# d100_zm1000_rev_b.net
KiCad netlist of a schematic drawn in EAGLE
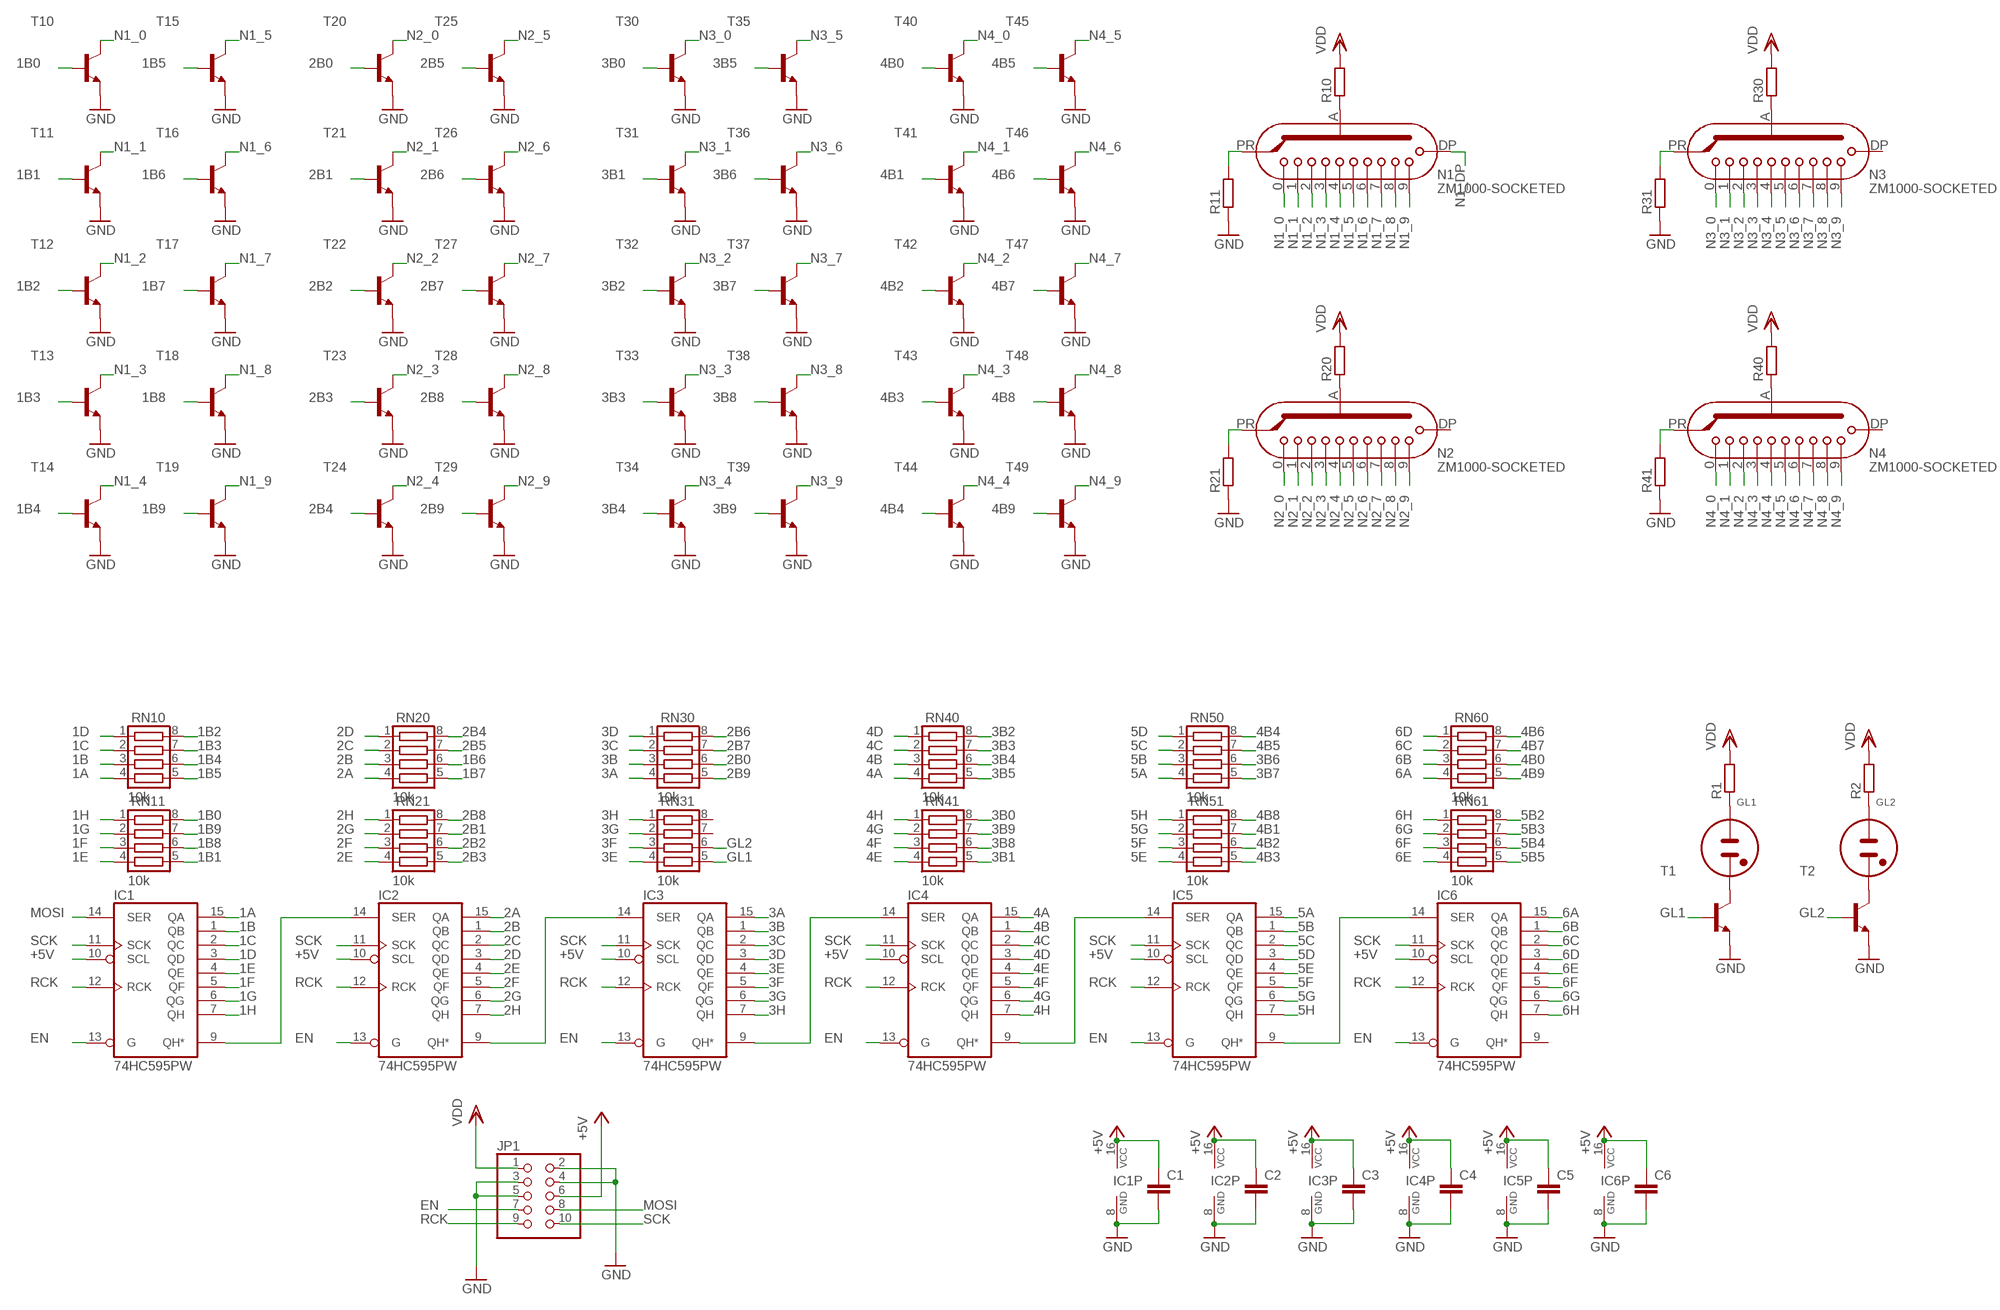
[diagram p0: schematic, sheet 1]

(export (version "E")
  (design (tool "Eeschema 10.0.6"))
  (components
    (comp (ref "C1")
      (value "C-EUC0603")
      (footprint "eagle-import:C0603")
      (libsource (lib "eagle-import") (part "C-EUC0603"))
    )
    (comp (ref "C2")
      (value "C-EUC0603")
      (footprint "eagle-import:C0603")
      (libsource (lib "eagle-import") (part "C-EUC0603"))
    )
    (comp (ref "C3")
      (value "C-EUC0603")
      (footprint "eagle-import:C0603")
      (libsource (lib "eagle-import") (part "C-EUC0603"))
    )
    (comp (ref "C4")
      (value "C-EUC0603")
      (footprint "eagle-import:C0603")
      (libsource (lib "eagle-import") (part "C-EUC0603"))
    )
    (comp (ref "C5")
      (value "C-EUC0603")
      (footprint "eagle-import:C0603")
      (libsource (lib "eagle-import") (part "C-EUC0603"))
    )
    (comp (ref "C6")
      (value "C-EUC0603")
      (footprint "eagle-import:C0603")
      (libsource (lib "eagle-import") (part "C-EUC0603"))
    )
    (comp (ref "GL1")
      (value "NE2-NEON-BULB-DRILL")
      (footprint "eagle-import:NE2-NEON-BULB-DRILL")
      (libsource (lib "eagle-import") (part "NE2-NEON-BULB-DRILL"))
    )
    (comp (ref "GL2")
      (value "NE2-NEON-BULB-DRILL")
      (footprint "eagle-import:NE2-NEON-BULB-DRILL")
      (libsource (lib "eagle-import") (part "NE2-NEON-BULB-DRILL"))
    )
    (comp (ref "IC1")
      (value "74HC595PW")
      (footprint "eagle-import:TSSOP16")
      (libsource (lib "eagle-import") (part "74595PWHC"))
    )
    (comp (ref "IC2")
      (value "74HC595PW")
      (footprint "eagle-import:TSSOP16")
      (libsource (lib "eagle-import") (part "74595PWHC"))
    )
    (comp (ref "IC3")
      (value "74HC595PW")
      (footprint "eagle-import:TSSOP16")
      (libsource (lib "eagle-import") (part "74595PWHC"))
    )
    (comp (ref "IC4")
      (value "74HC595PW")
      (footprint "eagle-import:TSSOP16")
      (libsource (lib "eagle-import") (part "74595PWHC"))
    )
    (comp (ref "IC5")
      (value "74HC595PW")
      (footprint "eagle-import:TSSOP16")
      (libsource (lib "eagle-import") (part "74595PWHC"))
    )
    (comp (ref "IC6")
      (value "74HC595PW")
      (footprint "eagle-import:TSSOP16")
      (libsource (lib "eagle-import") (part "74595PWHC"))
    )
    (comp (ref "JP1")
      (value "PINHD-2X5_2.54-SMD")
      (footprint "eagle-import:2X05SMD")
      (libsource (lib "eagle-import") (part "PINHD-2X5_2.54-SMD"))
    )
    (comp (ref "N1")
      (value "ZM1000-SOCKETED")
      (footprint "eagle-import:ZM1000-SOCKETED")
      (libsource (lib "eagle-import") (part "ZM1000-SOCKETED"))
    )
    (comp (ref "N2")
      (value "ZM1000-SOCKETED")
      (footprint "eagle-import:ZM1000-SOCKETED")
      (libsource (lib "eagle-import") (part "ZM1000-SOCKETED"))
    )
    (comp (ref "N3")
      (value "ZM1000-SOCKETED")
      (footprint "eagle-import:ZM1000-SOCKETED")
      (libsource (lib "eagle-import") (part "ZM1000-SOCKETED"))
    )
    (comp (ref "N4")
      (value "ZM1000-SOCKETED")
      (footprint "eagle-import:ZM1000-SOCKETED")
      (libsource (lib "eagle-import") (part "ZM1000-SOCKETED"))
    )
    (comp (ref "R1")
      (value "R-EU_R0603")
      (footprint "eagle-import:R0603")
      (libsource (lib "eagle-import") (part "R-EU_R0603"))
    )
    (comp (ref "R2")
      (value "R-EU_R0603")
      (footprint "eagle-import:R0603")
      (libsource (lib "eagle-import") (part "R-EU_R0603"))
    )
    (comp (ref "R10")
      (value "R-EU_R0603")
      (footprint "eagle-import:R0603")
      (libsource (lib "eagle-import") (part "R-EU_R0603"))
    )
    (comp (ref "R11")
      (value "R-EU_R0603")
      (footprint "eagle-import:R0603")
      (libsource (lib "eagle-import") (part "R-EU_R0603"))
    )
    (comp (ref "R20")
      (value "R-EU_R0603")
      (footprint "eagle-import:R0603")
      (libsource (lib "eagle-import") (part "R-EU_R0603"))
    )
    (comp (ref "R21")
      (value "R-EU_R0603")
      (footprint "eagle-import:R0603")
      (libsource (lib "eagle-import") (part "R-EU_R0603"))
    )
    (comp (ref "R30")
      (value "R-EU_R0603")
      (footprint "eagle-import:R0603")
      (libsource (lib "eagle-import") (part "R-EU_R0603"))
    )
    (comp (ref "R31")
      (value "R-EU_R0603")
      (footprint "eagle-import:R0603")
      (libsource (lib "eagle-import") (part "R-EU_R0603"))
    )
    (comp (ref "R40")
      (value "R-EU_R0603")
      (footprint "eagle-import:R0603")
      (libsource (lib "eagle-import") (part "R-EU_R0603"))
    )
    (comp (ref "R41")
      (value "R-EU_R0603")
      (footprint "eagle-import:R0603")
      (libsource (lib "eagle-import") (part "R-EU_R0603"))
    )
    (comp (ref "RN10")
      (value "10k")
      (footprint "eagle-import:CTS742C083")
      (fields (field (name "OC_FARNELL") "unknown") (field (name "OC_NEWARK") "unknown"))
      (libsource (lib "eagle-import") (part "CTS742C083"))
    )
    (comp (ref "RN11")
      (value "10k")
      (footprint "eagle-import:CTS742C083")
      (fields (field (name "OC_FARNELL") "unknown") (field (name "OC_NEWARK") "unknown"))
      (libsource (lib "eagle-import") (part "CTS742C083"))
    )
    (comp (ref "RN20")
      (value "10k")
      (footprint "eagle-import:CTS742C083")
      (fields (field (name "OC_FARNELL") "unknown") (field (name "OC_NEWARK") "unknown"))
      (libsource (lib "eagle-import") (part "CTS742C083"))
    )
    (comp (ref "RN21")
      (value "10k")
      (footprint "eagle-import:CTS742C083")
      (fields (field (name "OC_FARNELL") "unknown") (field (name "OC_NEWARK") "unknown"))
      (libsource (lib "eagle-import") (part "CTS742C083"))
    )
    (comp (ref "RN30")
      (value "10k")
      (footprint "eagle-import:CTS742C083")
      (fields (field (name "OC_FARNELL") "unknown") (field (name "OC_NEWARK") "unknown"))
      (libsource (lib "eagle-import") (part "CTS742C083"))
    )
    (comp (ref "RN31")
      (value "10k")
      (footprint "eagle-import:CTS742C083")
      (fields (field (name "OC_FARNELL") "unknown") (field (name "OC_NEWARK") "unknown"))
      (libsource (lib "eagle-import") (part "CTS742C083"))
    )
    (comp (ref "RN40")
      (value "10k")
      (footprint "eagle-import:CTS742C083")
      (fields (field (name "OC_FARNELL") "unknown") (field (name "OC_NEWARK") "unknown"))
      (libsource (lib "eagle-import") (part "CTS742C083"))
    )
    (comp (ref "RN41")
      (value "10k")
      (footprint "eagle-import:CTS742C083")
      (fields (field (name "OC_FARNELL") "unknown") (field (name "OC_NEWARK") "unknown"))
      (libsource (lib "eagle-import") (part "CTS742C083"))
    )
    (comp (ref "RN50")
      (value "10k")
      (footprint "eagle-import:CTS742C083")
      (fields (field (name "OC_FARNELL") "unknown") (field (name "OC_NEWARK") "unknown"))
      (libsource (lib "eagle-import") (part "CTS742C083"))
    )
    (comp (ref "RN51")
      (value "10k")
      (footprint "eagle-import:CTS742C083")
      (fields (field (name "OC_FARNELL") "unknown") (field (name "OC_NEWARK") "unknown"))
      (libsource (lib "eagle-import") (part "CTS742C083"))
    )
    (comp (ref "RN60")
      (value "10k")
      (footprint "eagle-import:CTS742C083")
      (fields (field (name "OC_FARNELL") "unknown") (field (name "OC_NEWARK") "unknown"))
      (libsource (lib "eagle-import") (part "CTS742C083"))
    )
    (comp (ref "RN61")
      (value "10k")
      (footprint "eagle-import:CTS742C083")
      (fields (field (name "OC_FARNELL") "unknown") (field (name "OC_NEWARK") "unknown"))
      (libsource (lib "eagle-import") (part "CTS742C083"))
    )
    (comp (ref "T1")
      (value "SMBTA42")
      (footprint "eagle-import:SOT23")
      (libsource (lib "eagle-import") (part "SMBTA42"))
    )
    (comp (ref "T2")
      (value "SMBTA42")
      (footprint "eagle-import:SOT23")
      (libsource (lib "eagle-import") (part "SMBTA42"))
    )
    (comp (ref "T10")
      (value "SMBTA42")
      (footprint "eagle-import:SOT23")
      (libsource (lib "eagle-import") (part "SMBTA42"))
    )
    (comp (ref "T11")
      (value "SMBTA42")
      (footprint "eagle-import:SOT23")
      (libsource (lib "eagle-import") (part "SMBTA42"))
    )
    (comp (ref "T12")
      (value "SMBTA42")
      (footprint "eagle-import:SOT23")
      (libsource (lib "eagle-import") (part "SMBTA42"))
    )
    (comp (ref "T13")
      (value "SMBTA42")
      (footprint "eagle-import:SOT23")
      (libsource (lib "eagle-import") (part "SMBTA42"))
    )
    (comp (ref "T14")
      (value "SMBTA42")
      (footprint "eagle-import:SOT23")
      (libsource (lib "eagle-import") (part "SMBTA42"))
    )
    (comp (ref "T15")
      (value "SMBTA42")
      (footprint "eagle-import:SOT23")
      (libsource (lib "eagle-import") (part "SMBTA42"))
    )
    (comp (ref "T16")
      (value "SMBTA42")
      (footprint "eagle-import:SOT23")
      (libsource (lib "eagle-import") (part "SMBTA42"))
    )
    (comp (ref "T17")
      (value "SMBTA42")
      (footprint "eagle-import:SOT23")
      (libsource (lib "eagle-import") (part "SMBTA42"))
    )
    (comp (ref "T18")
      (value "SMBTA42")
      (footprint "eagle-import:SOT23")
      (libsource (lib "eagle-import") (part "SMBTA42"))
    )
    (comp (ref "T19")
      (value "SMBTA42")
      (footprint "eagle-import:SOT23")
      (libsource (lib "eagle-import") (part "SMBTA42"))
    )
    (comp (ref "T20")
      (value "SMBTA42")
      (footprint "eagle-import:SOT23")
      (libsource (lib "eagle-import") (part "SMBTA42"))
    )
    (comp (ref "T21")
      (value "SMBTA42")
      (footprint "eagle-import:SOT23")
      (libsource (lib "eagle-import") (part "SMBTA42"))
    )
    (comp (ref "T22")
      (value "SMBTA42")
      (footprint "eagle-import:SOT23")
      (libsource (lib "eagle-import") (part "SMBTA42"))
    )
    (comp (ref "T23")
      (value "SMBTA42")
      (footprint "eagle-import:SOT23")
      (libsource (lib "eagle-import") (part "SMBTA42"))
    )
    (comp (ref "T24")
      (value "SMBTA42")
      (footprint "eagle-import:SOT23")
      (libsource (lib "eagle-import") (part "SMBTA42"))
    )
    (comp (ref "T25")
      (value "SMBTA42")
      (footprint "eagle-import:SOT23")
      (libsource (lib "eagle-import") (part "SMBTA42"))
    )
    (comp (ref "T26")
      (value "SMBTA42")
      (footprint "eagle-import:SOT23")
      (libsource (lib "eagle-import") (part "SMBTA42"))
    )
    (comp (ref "T27")
      (value "SMBTA42")
      (footprint "eagle-import:SOT23")
      (libsource (lib "eagle-import") (part "SMBTA42"))
    )
    (comp (ref "T28")
      (value "SMBTA42")
      (footprint "eagle-import:SOT23")
      (libsource (lib "eagle-import") (part "SMBTA42"))
    )
    (comp (ref "T29")
      (value "SMBTA42")
      (footprint "eagle-import:SOT23")
      (libsource (lib "eagle-import") (part "SMBTA42"))
    )
    (comp (ref "T30")
      (value "SMBTA42")
      (footprint "eagle-import:SOT23")
      (libsource (lib "eagle-import") (part "SMBTA42"))
    )
    (comp (ref "T31")
      (value "SMBTA42")
      (footprint "eagle-import:SOT23")
      (libsource (lib "eagle-import") (part "SMBTA42"))
    )
    (comp (ref "T32")
      (value "SMBTA42")
      (footprint "eagle-import:SOT23")
      (libsource (lib "eagle-import") (part "SMBTA42"))
    )
    (comp (ref "T33")
      (value "SMBTA42")
      (footprint "eagle-import:SOT23")
      (libsource (lib "eagle-import") (part "SMBTA42"))
    )
    (comp (ref "T34")
      (value "SMBTA42")
      (footprint "eagle-import:SOT23")
      (libsource (lib "eagle-import") (part "SMBTA42"))
    )
    (comp (ref "T35")
      (value "SMBTA42")
      (footprint "eagle-import:SOT23")
      (libsource (lib "eagle-import") (part "SMBTA42"))
    )
    (comp (ref "T36")
      (value "SMBTA42")
      (footprint "eagle-import:SOT23")
      (libsource (lib "eagle-import") (part "SMBTA42"))
    )
    (comp (ref "T37")
      (value "SMBTA42")
      (footprint "eagle-import:SOT23")
      (libsource (lib "eagle-import") (part "SMBTA42"))
    )
    (comp (ref "T38")
      (value "SMBTA42")
      (footprint "eagle-import:SOT23")
      (libsource (lib "eagle-import") (part "SMBTA42"))
    )
    (comp (ref "T39")
      (value "SMBTA42")
      (footprint "eagle-import:SOT23")
      (libsource (lib "eagle-import") (part "SMBTA42"))
    )
    (comp (ref "T40")
      (value "SMBTA42")
      (footprint "eagle-import:SOT23")
      (libsource (lib "eagle-import") (part "SMBTA42"))
    )
    (comp (ref "T41")
      (value "SMBTA42")
      (footprint "eagle-import:SOT23")
      (libsource (lib "eagle-import") (part "SMBTA42"))
    )
    (comp (ref "T42")
      (value "SMBTA42")
      (footprint "eagle-import:SOT23")
      (libsource (lib "eagle-import") (part "SMBTA42"))
    )
    (comp (ref "T43")
      (value "SMBTA42")
      (footprint "eagle-import:SOT23")
      (libsource (lib "eagle-import") (part "SMBTA42"))
    )
    (comp (ref "T44")
      (value "SMBTA42")
      (footprint "eagle-import:SOT23")
      (libsource (lib "eagle-import") (part "SMBTA42"))
    )
    (comp (ref "T45")
      (value "SMBTA42")
      (footprint "eagle-import:SOT23")
      (libsource (lib "eagle-import") (part "SMBTA42"))
    )
    (comp (ref "T46")
      (value "SMBTA42")
      (footprint "eagle-import:SOT23")
      (libsource (lib "eagle-import") (part "SMBTA42"))
    )
    (comp (ref "T47")
      (value "SMBTA42")
      (footprint "eagle-import:SOT23")
      (libsource (lib "eagle-import") (part "SMBTA42"))
    )
    (comp (ref "T48")
      (value "SMBTA42")
      (footprint "eagle-import:SOT23")
      (libsource (lib "eagle-import") (part "SMBTA42"))
    )
    (comp (ref "T49")
      (value "SMBTA42")
      (footprint "eagle-import:SOT23")
      (libsource (lib "eagle-import") (part "SMBTA42"))
    )
  )
  (nets
    (net (code "1") (name "+5V") (class "Default")
      (node (ref "C1") (pin "1") (pinfunction "1_1") (pintype "passive"))
      (node (ref "C2") (pin "1") (pinfunction "1_1") (pintype "passive"))
      (node (ref "C3") (pin "1") (pinfunction "1_1") (pintype "passive"))
      (node (ref "C4") (pin "1") (pinfunction "1_1") (pintype "passive"))
      (node (ref "C5") (pin "1") (pinfunction "1_1") (pintype "passive"))
      (node (ref "C6") (pin "1") (pinfunction "1_1") (pintype "passive"))
      (node (ref "IC1") (pin "10") (pinfunction "SCL_10") (pintype "input"))
      (node (ref "IC1") (pin "16") (pinfunction "VCC_16") (pintype "power_in"))
      (node (ref "IC2") (pin "10") (pinfunction "SCL_10") (pintype "input"))
      (node (ref "IC2") (pin "16") (pinfunction "VCC_16") (pintype "power_in"))
      (node (ref "IC3") (pin "10") (pinfunction "SCL_10") (pintype "input"))
      (node (ref "IC3") (pin "16") (pinfunction "VCC_16") (pintype "power_in"))
      (node (ref "IC4") (pin "10") (pinfunction "SCL_10") (pintype "input"))
      (node (ref "IC4") (pin "16") (pinfunction "VCC_16") (pintype "power_in"))
      (node (ref "IC5") (pin "10") (pinfunction "SCL_10") (pintype "input"))
      (node (ref "IC5") (pin "16") (pinfunction "VCC_16") (pintype "power_in"))
      (node (ref "IC6") (pin "10") (pinfunction "SCL_10") (pintype "input"))
      (node (ref "IC6") (pin "16") (pinfunction "VCC_16") (pintype "power_in"))
      (node (ref "JP1") (pin "6") (pinfunction "6_6") (pintype "passive"))
    )
    (net (code "2") (name "/1A") (class "Default")
      (node (ref "IC1") (pin "15") (pinfunction "QA_15") (pintype "tri_state"))
      (node (ref "RN10") (pin "4") (pinfunction "4_4") (pintype "passive"))
    )
    (net (code "3") (name "/1B") (class "Default")
      (node (ref "IC1") (pin "1") (pinfunction "QB_1") (pintype "tri_state"))
      (node (ref "RN10") (pin "3") (pinfunction "3_3") (pintype "passive"))
    )
    (net (code "4") (name "/1B0") (class "Default")
      (node (ref "RN11") (pin "8") (pinfunction "8_8") (pintype "passive"))
      (node (ref "T10") (pin "1") (pinfunction "B_1") (pintype "passive"))
    )
    (net (code "5") (name "/1B1") (class "Default")
      (node (ref "RN11") (pin "5") (pinfunction "5_5") (pintype "passive"))
      (node (ref "T11") (pin "1") (pinfunction "B_1") (pintype "passive"))
    )
    (net (code "6") (name "/1B2") (class "Default")
      (node (ref "RN10") (pin "8") (pinfunction "8_8") (pintype "passive"))
      (node (ref "T12") (pin "1") (pinfunction "B_1") (pintype "passive"))
    )
    (net (code "7") (name "/1B3") (class "Default")
      (node (ref "RN10") (pin "7") (pinfunction "7_7") (pintype "passive"))
      (node (ref "T13") (pin "1") (pinfunction "B_1") (pintype "passive"))
    )
    (net (code "8") (name "/1B4") (class "Default")
      (node (ref "RN10") (pin "6") (pinfunction "6_6") (pintype "passive"))
      (node (ref "T14") (pin "1") (pinfunction "B_1") (pintype "passive"))
    )
    (net (code "9") (name "/1B5") (class "Default")
      (node (ref "RN10") (pin "5") (pinfunction "5_5") (pintype "passive"))
      (node (ref "T15") (pin "1") (pinfunction "B_1") (pintype "passive"))
    )
    (net (code "10") (name "/1B6") (class "Default")
      (node (ref "RN20") (pin "6") (pinfunction "6_6") (pintype "passive"))
      (node (ref "T16") (pin "1") (pinfunction "B_1") (pintype "passive"))
    )
    (net (code "11") (name "/1B7") (class "Default")
      (node (ref "RN20") (pin "5") (pinfunction "5_5") (pintype "passive"))
      (node (ref "T17") (pin "1") (pinfunction "B_1") (pintype "passive"))
    )
    (net (code "12") (name "/1B8") (class "Default")
      (node (ref "RN11") (pin "6") (pinfunction "6_6") (pintype "passive"))
      (node (ref "T18") (pin "1") (pinfunction "B_1") (pintype "passive"))
    )
    (net (code "13") (name "/1B9") (class "Default")
      (node (ref "RN11") (pin "7") (pinfunction "7_7") (pintype "passive"))
      (node (ref "T19") (pin "1") (pinfunction "B_1") (pintype "passive"))
    )
    (net (code "14") (name "/1C") (class "Default")
      (node (ref "IC1") (pin "2") (pinfunction "QC_2") (pintype "tri_state"))
      (node (ref "RN10") (pin "2") (pinfunction "2_2") (pintype "passive"))
    )
    (net (code "15") (name "/1D") (class "Default")
      (node (ref "IC1") (pin "3") (pinfunction "QD_3") (pintype "tri_state"))
      (node (ref "RN10") (pin "1") (pinfunction "1_1") (pintype "passive"))
    )
    (net (code "16") (name "/1E") (class "Default")
      (node (ref "IC1") (pin "4") (pinfunction "QE_4") (pintype "tri_state"))
      (node (ref "RN11") (pin "4") (pinfunction "4_4") (pintype "passive"))
    )
    (net (code "17") (name "/1F") (class "Default")
      (node (ref "IC1") (pin "5") (pinfunction "QF_5") (pintype "tri_state"))
      (node (ref "RN11") (pin "3") (pinfunction "3_3") (pintype "passive"))
    )
    (net (code "18") (name "/1G") (class "Default")
      (node (ref "IC1") (pin "6") (pinfunction "QG_6") (pintype "tri_state"))
      (node (ref "RN11") (pin "2") (pinfunction "2_2") (pintype "passive"))
    )
    (net (code "19") (name "/1H") (class "Default")
      (node (ref "IC1") (pin "7") (pinfunction "QH_7") (pintype "tri_state"))
      (node (ref "RN11") (pin "1") (pinfunction "1_1") (pintype "passive"))
    )
    (net (code "20") (name "/2A") (class "Default")
      (node (ref "IC2") (pin "15") (pinfunction "QA_15") (pintype "tri_state"))
      (node (ref "RN20") (pin "4") (pinfunction "4_4") (pintype "passive"))
    )
    (net (code "21") (name "/2B") (class "Default")
      (node (ref "IC2") (pin "1") (pinfunction "QB_1") (pintype "tri_state"))
      (node (ref "RN20") (pin "3") (pinfunction "3_3") (pintype "passive"))
    )
    (net (code "22") (name "/2B0") (class "Default")
      (node (ref "RN30") (pin "6") (pinfunction "6_6") (pintype "passive"))
      (node (ref "T20") (pin "1") (pinfunction "B_1") (pintype "passive"))
    )
    (net (code "23") (name "/2B1") (class "Default")
      (node (ref "RN21") (pin "7") (pinfunction "7_7") (pintype "passive"))
      (node (ref "T21") (pin "1") (pinfunction "B_1") (pintype "passive"))
    )
    (net (code "24") (name "/2B2") (class "Default")
      (node (ref "RN21") (pin "6") (pinfunction "6_6") (pintype "passive"))
      (node (ref "T22") (pin "1") (pinfunction "B_1") (pintype "passive"))
    )
    (net (code "25") (name "/2B3") (class "Default")
      (node (ref "RN21") (pin "5") (pinfunction "5_5") (pintype "passive"))
      (node (ref "T23") (pin "1") (pinfunction "B_1") (pintype "passive"))
    )
    (net (code "26") (name "/2B4") (class "Default")
      (node (ref "RN20") (pin "8") (pinfunction "8_8") (pintype "passive"))
      (node (ref "T24") (pin "1") (pinfunction "B_1") (pintype "passive"))
    )
    (net (code "27") (name "/2B5") (class "Default")
      (node (ref "RN20") (pin "7") (pinfunction "7_7") (pintype "passive"))
      (node (ref "T25") (pin "1") (pinfunction "B_1") (pintype "passive"))
    )
    (net (code "28") (name "/2B6") (class "Default")
      (node (ref "RN30") (pin "8") (pinfunction "8_8") (pintype "passive"))
      (node (ref "T26") (pin "1") (pinfunction "B_1") (pintype "passive"))
    )
    (net (code "29") (name "/2B7") (class "Default")
      (node (ref "RN30") (pin "7") (pinfunction "7_7") (pintype "passive"))
      (node (ref "T27") (pin "1") (pinfunction "B_1") (pintype "passive"))
    )
    (net (code "30") (name "/2B8") (class "Default")
      (node (ref "RN21") (pin "8") (pinfunction "8_8") (pintype "passive"))
      (node (ref "T28") (pin "1") (pinfunction "B_1") (pintype "passive"))
    )
    (net (code "31") (name "/2B9") (class "Default")
      (node (ref "RN30") (pin "5") (pinfunction "5_5") (pintype "passive"))
      (node (ref "T29") (pin "1") (pinfunction "B_1") (pintype "passive"))
    )
    (net (code "32") (name "/2C") (class "Default")
      (node (ref "IC2") (pin "2") (pinfunction "QC_2") (pintype "tri_state"))
      (node (ref "RN20") (pin "2") (pinfunction "2_2") (pintype "passive"))
    )
    (net (code "33") (name "/2D") (class "Default")
      (node (ref "IC2") (pin "3") (pinfunction "QD_3") (pintype "tri_state"))
      (node (ref "RN20") (pin "1") (pinfunction "1_1") (pintype "passive"))
    )
    (net (code "34") (name "/2E") (class "Default")
      (node (ref "IC2") (pin "4") (pinfunction "QE_4") (pintype "tri_state"))
      (node (ref "RN21") (pin "4") (pinfunction "4_4") (pintype "passive"))
    )
    (net (code "35") (name "/2F") (class "Default")
      (node (ref "IC2") (pin "5") (pinfunction "QF_5") (pintype "tri_state"))
      (node (ref "RN21") (pin "3") (pinfunction "3_3") (pintype "passive"))
    )
    (net (code "36") (name "/2G") (class "Default")
      (node (ref "IC2") (pin "6") (pinfunction "QG_6") (pintype "tri_state"))
      (node (ref "RN21") (pin "2") (pinfunction "2_2") (pintype "passive"))
    )
    (net (code "37") (name "/2H") (class "Default")
      (node (ref "IC2") (pin "7") (pinfunction "QH_7") (pintype "tri_state"))
      (node (ref "RN21") (pin "1") (pinfunction "1_1") (pintype "passive"))
    )
    (net (code "38") (name "/3A") (class "Default")
      (node (ref "IC3") (pin "15") (pinfunction "QA_15") (pintype "tri_state"))
      (node (ref "RN30") (pin "4") (pinfunction "4_4") (pintype "passive"))
    )
    (net (code "39") (name "/3B") (class "Default")
      (node (ref "IC3") (pin "1") (pinfunction "QB_1") (pintype "tri_state"))
      (node (ref "RN30") (pin "3") (pinfunction "3_3") (pintype "passive"))
    )
    (net (code "40") (name "/3B0") (class "Default")
      (node (ref "RN41") (pin "8") (pinfunction "8_8") (pintype "passive"))
      (node (ref "T30") (pin "1") (pinfunction "B_1") (pintype "passive"))
    )
    (net (code "41") (name "/3B1") (class "Default")
      (node (ref "RN41") (pin "5") (pinfunction "5_5") (pintype "passive"))
      (node (ref "T31") (pin "1") (pinfunction "B_1") (pintype "passive"))
    )
    (net (code "42") (name "/3B2") (class "Default")
      (node (ref "RN40") (pin "8") (pinfunction "8_8") (pintype "passive"))
      (node (ref "T32") (pin "1") (pinfunction "B_1") (pintype "passive"))
    )
    (net (code "43") (name "/3B3") (class "Default")
      (node (ref "RN40") (pin "7") (pinfunction "7_7") (pintype "passive"))
      (node (ref "T33") (pin "1") (pinfunction "B_1") (pintype "passive"))
    )
    (net (code "44") (name "/3B4") (class "Default")
      (node (ref "RN40") (pin "6") (pinfunction "6_6") (pintype "passive"))
      (node (ref "T34") (pin "1") (pinfunction "B_1") (pintype "passive"))
    )
    (net (code "45") (name "/3B5") (class "Default")
      (node (ref "RN40") (pin "5") (pinfunction "5_5") (pintype "passive"))
      (node (ref "T35") (pin "1") (pinfunction "B_1") (pintype "passive"))
    )
    (net (code "46") (name "/3B6") (class "Default")
      (node (ref "RN50") (pin "6") (pinfunction "6_6") (pintype "passive"))
      (node (ref "T36") (pin "1") (pinfunction "B_1") (pintype "passive"))
    )
    (net (code "47") (name "/3B7") (class "Default")
      (node (ref "RN50") (pin "5") (pinfunction "5_5") (pintype "passive"))
      (node (ref "T37") (pin "1") (pinfunction "B_1") (pintype "passive"))
    )
    (net (code "48") (name "/3B8") (class "Default")
      (node (ref "RN41") (pin "6") (pinfunction "6_6") (pintype "passive"))
      (node (ref "T38") (pin "1") (pinfunction "B_1") (pintype "passive"))
    )
    (net (code "49") (name "/3B9") (class "Default")
      (node (ref "RN41") (pin "7") (pinfunction "7_7") (pintype "passive"))
      (node (ref "T39") (pin "1") (pinfunction "B_1") (pintype "passive"))
    )
    (net (code "50") (name "/3C") (class "Default")
      (node (ref "IC3") (pin "2") (pinfunction "QC_2") (pintype "tri_state"))
      (node (ref "RN30") (pin "2") (pinfunction "2_2") (pintype "passive"))
    )
    (net (code "51") (name "/3D") (class "Default")
      (node (ref "IC3") (pin "3") (pinfunction "QD_3") (pintype "tri_state"))
      (node (ref "RN30") (pin "1") (pinfunction "1_1") (pintype "passive"))
    )
    (net (code "52") (name "/3E") (class "Default")
      (node (ref "IC3") (pin "4") (pinfunction "QE_4") (pintype "tri_state"))
      (node (ref "RN31") (pin "4") (pinfunction "4_4") (pintype "passive"))
    )
    (net (code "53") (name "/3F") (class "Default")
      (node (ref "IC3") (pin "5") (pinfunction "QF_5") (pintype "tri_state"))
      (node (ref "RN31") (pin "3") (pinfunction "3_3") (pintype "passive"))
    )
    (net (code "54") (name "/3G") (class "Default")
      (node (ref "IC3") (pin "6") (pinfunction "QG_6") (pintype "tri_state"))
      (node (ref "RN31") (pin "2") (pinfunction "2_2") (pintype "passive"))
    )
    (net (code "55") (name "/3H") (class "Default")
      (node (ref "IC3") (pin "7") (pinfunction "QH_7") (pintype "tri_state"))
      (node (ref "RN31") (pin "1") (pinfunction "1_1") (pintype "passive"))
    )
    (net (code "56") (name "/4A") (class "Default")
      (node (ref "IC4") (pin "15") (pinfunction "QA_15") (pintype "tri_state"))
      (node (ref "RN40") (pin "4") (pinfunction "4_4") (pintype "passive"))
    )
    (net (code "57") (name "/4B") (class "Default")
      (node (ref "IC4") (pin "1") (pinfunction "QB_1") (pintype "tri_state"))
      (node (ref "RN40") (pin "3") (pinfunction "3_3") (pintype "passive"))
    )
    (net (code "58") (name "/4B0") (class "Default")
      (node (ref "RN60") (pin "6") (pinfunction "6_6") (pintype "passive"))
      (node (ref "T40") (pin "1") (pinfunction "B_1") (pintype "passive"))
    )
    (net (code "59") (name "/4B1") (class "Default")
      (node (ref "RN51") (pin "7") (pinfunction "7_7") (pintype "passive"))
      (node (ref "T41") (pin "1") (pinfunction "B_1") (pintype "passive"))
    )
    (net (code "60") (name "/4B2") (class "Default")
      (node (ref "RN51") (pin "6") (pinfunction "6_6") (pintype "passive"))
      (node (ref "T42") (pin "1") (pinfunction "B_1") (pintype "passive"))
    )
    (net (code "61") (name "/4B3") (class "Default")
      (node (ref "RN51") (pin "5") (pinfunction "5_5") (pintype "passive"))
      (node (ref "T43") (pin "1") (pinfunction "B_1") (pintype "passive"))
    )
    (net (code "62") (name "/4B4") (class "Default")
      (node (ref "RN50") (pin "8") (pinfunction "8_8") (pintype "passive"))
      (node (ref "T44") (pin "1") (pinfunction "B_1") (pintype "passive"))
    )
    (net (code "63") (name "/4B5") (class "Default")
      (node (ref "RN50") (pin "7") (pinfunction "7_7") (pintype "passive"))
      (node (ref "T45") (pin "1") (pinfunction "B_1") (pintype "passive"))
    )
    (net (code "64") (name "/4B6") (class "Default")
      (node (ref "RN60") (pin "8") (pinfunction "8_8") (pintype "passive"))
      (node (ref "T46") (pin "1") (pinfunction "B_1") (pintype "passive"))
    )
    (net (code "65") (name "/4B7") (class "Default")
      (node (ref "RN60") (pin "7") (pinfunction "7_7") (pintype "passive"))
      (node (ref "T47") (pin "1") (pinfunction "B_1") (pintype "passive"))
    )
    (net (code "66") (name "/4B8") (class "Default")
      (node (ref "RN51") (pin "8") (pinfunction "8_8") (pintype "passive"))
      (node (ref "T48") (pin "1") (pinfunction "B_1") (pintype "passive"))
    )
    (net (code "67") (name "/4B9") (class "Default")
      (node (ref "RN60") (pin "5") (pinfunction "5_5") (pintype "passive"))
      (node (ref "T49") (pin "1") (pinfunction "B_1") (pintype "passive"))
    )
    (net (code "68") (name "/4C") (class "Default")
      (node (ref "IC4") (pin "2") (pinfunction "QC_2") (pintype "tri_state"))
      (node (ref "RN40") (pin "2") (pinfunction "2_2") (pintype "passive"))
    )
    (net (code "69") (name "/4D") (class "Default")
      (node (ref "IC4") (pin "3") (pinfunction "QD_3") (pintype "tri_state"))
      (node (ref "RN40") (pin "1") (pinfunction "1_1") (pintype "passive"))
    )
    (net (code "70") (name "/4E") (class "Default")
      (node (ref "IC4") (pin "4") (pinfunction "QE_4") (pintype "tri_state"))
      (node (ref "RN41") (pin "4") (pinfunction "4_4") (pintype "passive"))
    )
    (net (code "71") (name "/4F") (class "Default")
      (node (ref "IC4") (pin "5") (pinfunction "QF_5") (pintype "tri_state"))
      (node (ref "RN41") (pin "3") (pinfunction "3_3") (pintype "passive"))
    )
    (net (code "72") (name "/4G") (class "Default")
      (node (ref "IC4") (pin "6") (pinfunction "QG_6") (pintype "tri_state"))
      (node (ref "RN41") (pin "2") (pinfunction "2_2") (pintype "passive"))
    )
    (net (code "73") (name "/4H") (class "Default")
      (node (ref "IC4") (pin "7") (pinfunction "QH_7") (pintype "tri_state"))
      (node (ref "RN41") (pin "1") (pinfunction "1_1") (pintype "passive"))
    )
    (net (code "74") (name "/5A") (class "Default")
      (node (ref "IC5") (pin "15") (pinfunction "QA_15") (pintype "tri_state"))
      (node (ref "RN50") (pin "4") (pinfunction "4_4") (pintype "passive"))
    )
    (net (code "75") (name "/5B") (class "Default")
      (node (ref "IC5") (pin "1") (pinfunction "QB_1") (pintype "tri_state"))
      (node (ref "RN50") (pin "3") (pinfunction "3_3") (pintype "passive"))
    )
    (net (code "76") (name "/5B2") (class "Default")
      (node (ref "RN61") (pin "8") (pinfunction "8_8") (pintype "passive"))
    )
    (net (code "77") (name "/5B3") (class "Default")
      (node (ref "RN61") (pin "7") (pinfunction "7_7") (pintype "passive"))
    )
    (net (code "78") (name "/5B4") (class "Default")
      (node (ref "RN61") (pin "6") (pinfunction "6_6") (pintype "passive"))
    )
    (net (code "79") (name "/5B5") (class "Default")
      (node (ref "RN61") (pin "5") (pinfunction "5_5") (pintype "passive"))
    )
    (net (code "80") (name "/5C") (class "Default")
      (node (ref "IC5") (pin "2") (pinfunction "QC_2") (pintype "tri_state"))
      (node (ref "RN50") (pin "2") (pinfunction "2_2") (pintype "passive"))
    )
    (net (code "81") (name "/5D") (class "Default")
      (node (ref "IC5") (pin "3") (pinfunction "QD_3") (pintype "tri_state"))
      (node (ref "RN50") (pin "1") (pinfunction "1_1") (pintype "passive"))
    )
    (net (code "82") (name "/5E") (class "Default")
      (node (ref "IC5") (pin "4") (pinfunction "QE_4") (pintype "tri_state"))
      (node (ref "RN51") (pin "4") (pinfunction "4_4") (pintype "passive"))
    )
    (net (code "83") (name "/5F") (class "Default")
      (node (ref "IC5") (pin "5") (pinfunction "QF_5") (pintype "tri_state"))
      (node (ref "RN51") (pin "3") (pinfunction "3_3") (pintype "passive"))
    )
    (net (code "84") (name "/5G") (class "Default")
      (node (ref "IC5") (pin "6") (pinfunction "QG_6") (pintype "tri_state"))
      (node (ref "RN51") (pin "2") (pinfunction "2_2") (pintype "passive"))
    )
    (net (code "85") (name "/5H") (class "Default")
      (node (ref "IC5") (pin "7") (pinfunction "QH_7") (pintype "tri_state"))
      (node (ref "RN51") (pin "1") (pinfunction "1_1") (pintype "passive"))
    )
    (net (code "86") (name "/6A") (class "Default")
      (node (ref "IC6") (pin "15") (pinfunction "QA_15") (pintype "tri_state"))
      (node (ref "RN60") (pin "4") (pinfunction "4_4") (pintype "passive"))
    )
    (net (code "87") (name "/6B") (class "Default")
      (node (ref "IC6") (pin "1") (pinfunction "QB_1") (pintype "tri_state"))
      (node (ref "RN60") (pin "3") (pinfunction "3_3") (pintype "passive"))
    )
    (net (code "88") (name "/6C") (class "Default")
      (node (ref "IC6") (pin "2") (pinfunction "QC_2") (pintype "tri_state"))
      (node (ref "RN60") (pin "2") (pinfunction "2_2") (pintype "passive"))
    )
    (net (code "89") (name "/6D") (class "Default")
      (node (ref "IC6") (pin "3") (pinfunction "QD_3") (pintype "tri_state"))
      (node (ref "RN60") (pin "1") (pinfunction "1_1") (pintype "passive"))
    )
    (net (code "90") (name "/6E") (class "Default")
      (node (ref "IC6") (pin "4") (pinfunction "QE_4") (pintype "tri_state"))
      (node (ref "RN61") (pin "4") (pinfunction "4_4") (pintype "passive"))
    )
    (net (code "91") (name "/6F") (class "Default")
      (node (ref "IC6") (pin "5") (pinfunction "QF_5") (pintype "tri_state"))
      (node (ref "RN61") (pin "3") (pinfunction "3_3") (pintype "passive"))
    )
    (net (code "92") (name "/6G") (class "Default")
      (node (ref "IC6") (pin "6") (pinfunction "QG_6") (pintype "tri_state"))
      (node (ref "RN61") (pin "2") (pinfunction "2_2") (pintype "passive"))
    )
    (net (code "93") (name "/6H") (class "Default")
      (node (ref "IC6") (pin "7") (pinfunction "QH_7") (pintype "tri_state"))
      (node (ref "RN61") (pin "1") (pinfunction "1_1") (pintype "passive"))
    )
    (net (code "94") (name "/EN") (class "Default")
      (node (ref "IC1") (pin "13") (pinfunction "G_13") (pintype "input"))
      (node (ref "IC2") (pin "13") (pinfunction "G_13") (pintype "input"))
      (node (ref "IC3") (pin "13") (pinfunction "G_13") (pintype "input"))
      (node (ref "IC4") (pin "13") (pinfunction "G_13") (pintype "input"))
      (node (ref "IC5") (pin "13") (pinfunction "G_13") (pintype "input"))
      (node (ref "IC6") (pin "13") (pinfunction "G_13") (pintype "input"))
      (node (ref "JP1") (pin "7") (pinfunction "7_7") (pintype "passive"))
    )
    (net (code "95") (name "/GL1") (class "Default")
      (node (ref "RN31") (pin "5") (pinfunction "5_5") (pintype "passive"))
      (node (ref "T1") (pin "1") (pinfunction "B_1") (pintype "passive"))
    )
    (net (code "96") (name "/GL2") (class "Default")
      (node (ref "RN31") (pin "6") (pinfunction "6_6") (pintype "passive"))
      (node (ref "T2") (pin "1") (pinfunction "B_1") (pintype "passive"))
    )
    (net (code "97") (name "/MOSI") (class "Default")
      (node (ref "IC1") (pin "14") (pinfunction "SER_14") (pintype "input"))
      (node (ref "JP1") (pin "8") (pinfunction "8_8") (pintype "passive"))
    )
    (net (code "98") (name "/N1_0") (class "Default")
      (node (ref "N1") (pin "K0") (pinfunction "0_K0") (pintype "bidirectional"))
      (node (ref "T10") (pin "3") (pinfunction "C_3") (pintype "passive"))
    )
    (net (code "99") (name "/N1_1") (class "Default")
      (node (ref "N1") (pin "K1") (pinfunction "1_K1") (pintype "bidirectional"))
      (node (ref "T11") (pin "3") (pinfunction "C_3") (pintype "passive"))
    )
    (net (code "100") (name "/N1_2") (class "Default")
      (node (ref "N1") (pin "K2") (pinfunction "2_K2") (pintype "bidirectional"))
      (node (ref "T12") (pin "3") (pinfunction "C_3") (pintype "passive"))
    )
    (net (code "101") (name "/N1_3") (class "Default")
      (node (ref "N1") (pin "K3") (pinfunction "3_K3") (pintype "bidirectional"))
      (node (ref "T13") (pin "3") (pinfunction "C_3") (pintype "passive"))
    )
    (net (code "102") (name "/N1_4") (class "Default")
      (node (ref "N1") (pin "K4") (pinfunction "4_K4") (pintype "bidirectional"))
      (node (ref "T14") (pin "3") (pinfunction "C_3") (pintype "passive"))
    )
    (net (code "103") (name "/N1_5") (class "Default")
      (node (ref "N1") (pin "K5") (pinfunction "5_K5") (pintype "bidirectional"))
      (node (ref "T15") (pin "3") (pinfunction "C_3") (pintype "passive"))
    )
    (net (code "104") (name "/N1_6") (class "Default")
      (node (ref "N1") (pin "K6") (pinfunction "6_K6") (pintype "bidirectional"))
      (node (ref "T16") (pin "3") (pinfunction "C_3") (pintype "passive"))
    )
    (net (code "105") (name "/N1_7") (class "Default")
      (node (ref "N1") (pin "K7") (pinfunction "7_K7") (pintype "bidirectional"))
      (node (ref "T17") (pin "3") (pinfunction "C_3") (pintype "passive"))
    )
    (net (code "106") (name "/N1_8") (class "Default")
      (node (ref "N1") (pin "K8") (pinfunction "8_K8") (pintype "bidirectional"))
      (node (ref "T18") (pin "3") (pinfunction "C_3") (pintype "passive"))
    )
    (net (code "107") (name "/N1_9") (class "Default")
      (node (ref "N1") (pin "K9") (pinfunction "9_K9") (pintype "bidirectional"))
      (node (ref "T19") (pin "3") (pinfunction "C_3") (pintype "passive"))
    )
    (net (code "108") (name "/N1_DP") (class "Default")
      (node (ref "N1") (pin "KDP") (pinfunction "DP_KDP") (pintype "bidirectional"))
    )
    (net (code "109") (name "/N2_0") (class "Default")
      (node (ref "N2") (pin "K0") (pinfunction "0_K0") (pintype "bidirectional"))
      (node (ref "T20") (pin "3") (pinfunction "C_3") (pintype "passive"))
    )
    (net (code "110") (name "/N2_1") (class "Default")
      (node (ref "N2") (pin "K1") (pinfunction "1_K1") (pintype "bidirectional"))
      (node (ref "T21") (pin "3") (pinfunction "C_3") (pintype "passive"))
    )
    (net (code "111") (name "/N2_2") (class "Default")
      (node (ref "N2") (pin "K2") (pinfunction "2_K2") (pintype "bidirectional"))
      (node (ref "T22") (pin "3") (pinfunction "C_3") (pintype "passive"))
    )
    (net (code "112") (name "/N2_3") (class "Default")
      (node (ref "N2") (pin "K3") (pinfunction "3_K3") (pintype "bidirectional"))
      (node (ref "T23") (pin "3") (pinfunction "C_3") (pintype "passive"))
    )
    (net (code "113") (name "/N2_4") (class "Default")
      (node (ref "N2") (pin "K4") (pinfunction "4_K4") (pintype "bidirectional"))
      (node (ref "T24") (pin "3") (pinfunction "C_3") (pintype "passive"))
    )
    (net (code "114") (name "/N2_5") (class "Default")
      (node (ref "N2") (pin "K5") (pinfunction "5_K5") (pintype "bidirectional"))
      (node (ref "T25") (pin "3") (pinfunction "C_3") (pintype "passive"))
    )
    (net (code "115") (name "/N2_6") (class "Default")
      (node (ref "N2") (pin "K6") (pinfunction "6_K6") (pintype "bidirectional"))
      (node (ref "T26") (pin "3") (pinfunction "C_3") (pintype "passive"))
    )
    (net (code "116") (name "/N2_7") (class "Default")
      (node (ref "N2") (pin "K7") (pinfunction "7_K7") (pintype "bidirectional"))
      (node (ref "T27") (pin "3") (pinfunction "C_3") (pintype "passive"))
    )
    (net (code "117") (name "/N2_8") (class "Default")
      (node (ref "N2") (pin "K8") (pinfunction "8_K8") (pintype "bidirectional"))
      (node (ref "T28") (pin "3") (pinfunction "C_3") (pintype "passive"))
    )
    (net (code "118") (name "/N2_9") (class "Default")
      (node (ref "N2") (pin "K9") (pinfunction "9_K9") (pintype "bidirectional"))
      (node (ref "T29") (pin "3") (pinfunction "C_3") (pintype "passive"))
    )
    (net (code "119") (name "/N3_0") (class "Default")
      (node (ref "N3") (pin "K0") (pinfunction "0_K0") (pintype "bidirectional"))
      (node (ref "T30") (pin "3") (pinfunction "C_3") (pintype "passive"))
    )
    (net (code "120") (name "/N3_1") (class "Default")
      (node (ref "N3") (pin "K1") (pinfunction "1_K1") (pintype "bidirectional"))
      (node (ref "T31") (pin "3") (pinfunction "C_3") (pintype "passive"))
    )
    (net (code "121") (name "/N3_2") (class "Default")
      (node (ref "N3") (pin "K2") (pinfunction "2_K2") (pintype "bidirectional"))
      (node (ref "T32") (pin "3") (pinfunction "C_3") (pintype "passive"))
    )
    (net (code "122") (name "/N3_3") (class "Default")
      (node (ref "N3") (pin "K3") (pinfunction "3_K3") (pintype "bidirectional"))
      (node (ref "T33") (pin "3") (pinfunction "C_3") (pintype "passive"))
    )
    (net (code "123") (name "/N3_4") (class "Default")
      (node (ref "N3") (pin "K4") (pinfunction "4_K4") (pintype "bidirectional"))
      (node (ref "T34") (pin "3") (pinfunction "C_3") (pintype "passive"))
    )
    (net (code "124") (name "/N3_5") (class "Default")
      (node (ref "N3") (pin "K5") (pinfunction "5_K5") (pintype "bidirectional"))
      (node (ref "T35") (pin "3") (pinfunction "C_3") (pintype "passive"))
    )
    (net (code "125") (name "/N3_6") (class "Default")
      (node (ref "N3") (pin "K6") (pinfunction "6_K6") (pintype "bidirectional"))
      (node (ref "T36") (pin "3") (pinfunction "C_3") (pintype "passive"))
    )
    (net (code "126") (name "/N3_7") (class "Default")
      (node (ref "N3") (pin "K7") (pinfunction "7_K7") (pintype "bidirectional"))
      (node (ref "T37") (pin "3") (pinfunction "C_3") (pintype "passive"))
    )
    (net (code "127") (name "/N3_8") (class "Default")
      (node (ref "N3") (pin "K8") (pinfunction "8_K8") (pintype "bidirectional"))
      (node (ref "T38") (pin "3") (pinfunction "C_3") (pintype "passive"))
    )
    (net (code "128") (name "/N3_9") (class "Default")
      (node (ref "N3") (pin "K9") (pinfunction "9_K9") (pintype "bidirectional"))
      (node (ref "T39") (pin "3") (pinfunction "C_3") (pintype "passive"))
    )
    (net (code "129") (name "/N4_0") (class "Default")
      (node (ref "N4") (pin "K0") (pinfunction "0_K0") (pintype "bidirectional"))
      (node (ref "T40") (pin "3") (pinfunction "C_3") (pintype "passive"))
    )
    (net (code "130") (name "/N4_1") (class "Default")
      (node (ref "N4") (pin "K1") (pinfunction "1_K1") (pintype "bidirectional"))
      (node (ref "T41") (pin "3") (pinfunction "C_3") (pintype "passive"))
    )
    (net (code "131") (name "/N4_2") (class "Default")
      (node (ref "N4") (pin "K2") (pinfunction "2_K2") (pintype "bidirectional"))
      (node (ref "T42") (pin "3") (pinfunction "C_3") (pintype "passive"))
    )
    (net (code "132") (name "/N4_3") (class "Default")
      (node (ref "N4") (pin "K3") (pinfunction "3_K3") (pintype "bidirectional"))
      (node (ref "T43") (pin "3") (pinfunction "C_3") (pintype "passive"))
    )
    (net (code "133") (name "/N4_4") (class "Default")
      (node (ref "N4") (pin "K4") (pinfunction "4_K4") (pintype "bidirectional"))
      (node (ref "T44") (pin "3") (pinfunction "C_3") (pintype "passive"))
    )
    (net (code "134") (name "/N4_5") (class "Default")
      (node (ref "N4") (pin "K5") (pinfunction "5_K5") (pintype "bidirectional"))
      (node (ref "T45") (pin "3") (pinfunction "C_3") (pintype "passive"))
    )
    (net (code "135") (name "/N4_6") (class "Default")
      (node (ref "N4") (pin "K6") (pinfunction "6_K6") (pintype "bidirectional"))
      (node (ref "T46") (pin "3") (pinfunction "C_3") (pintype "passive"))
    )
    (net (code "136") (name "/N4_7") (class "Default")
      (node (ref "N4") (pin "K7") (pinfunction "7_K7") (pintype "bidirectional"))
      (node (ref "T47") (pin "3") (pinfunction "C_3") (pintype "passive"))
    )
    (net (code "137") (name "/N4_8") (class "Default")
      (node (ref "N4") (pin "K8") (pinfunction "8_K8") (pintype "bidirectional"))
      (node (ref "T48") (pin "3") (pinfunction "C_3") (pintype "passive"))
    )
    (net (code "138") (name "/N4_9") (class "Default")
      (node (ref "N4") (pin "K9") (pinfunction "9_K9") (pintype "bidirectional"))
      (node (ref "T49") (pin "3") (pinfunction "C_3") (pintype "passive"))
    )
    (net (code "139") (name "/RCK") (class "Default")
      (node (ref "IC1") (pin "12") (pinfunction "RCK_12") (pintype "input"))
      (node (ref "IC2") (pin "12") (pinfunction "RCK_12") (pintype "input"))
      (node (ref "IC3") (pin "12") (pinfunction "RCK_12") (pintype "input"))
      (node (ref "IC4") (pin "12") (pinfunction "RCK_12") (pintype "input"))
      (node (ref "IC5") (pin "12") (pinfunction "RCK_12") (pintype "input"))
      (node (ref "IC6") (pin "12") (pinfunction "RCK_12") (pintype "input"))
      (node (ref "JP1") (pin "9") (pinfunction "9_9") (pintype "passive"))
    )
    (net (code "140") (name "/SCK") (class "Default")
      (node (ref "IC1") (pin "11") (pinfunction "SCK_11") (pintype "input"))
      (node (ref "IC2") (pin "11") (pinfunction "SCK_11") (pintype "input"))
      (node (ref "IC3") (pin "11") (pinfunction "SCK_11") (pintype "input"))
      (node (ref "IC4") (pin "11") (pinfunction "SCK_11") (pintype "input"))
      (node (ref "IC5") (pin "11") (pinfunction "SCK_11") (pintype "input"))
      (node (ref "IC6") (pin "11") (pinfunction "SCK_11") (pintype "input"))
      (node (ref "JP1") (pin "10") (pinfunction "10_10") (pintype "passive"))
    )
    (net (code "141") (name "GND") (class "Default")
      (node (ref "C1") (pin "2") (pinfunction "2_2") (pintype "passive"))
      (node (ref "C2") (pin "2") (pinfunction "2_2") (pintype "passive"))
      (node (ref "C3") (pin "2") (pinfunction "2_2") (pintype "passive"))
      (node (ref "C4") (pin "2") (pinfunction "2_2") (pintype "passive"))
      (node (ref "C5") (pin "2") (pinfunction "2_2") (pintype "passive"))
      (node (ref "C6") (pin "2") (pinfunction "2_2") (pintype "passive"))
      (node (ref "IC1") (pin "8") (pinfunction "GND_8") (pintype "power_in"))
      (node (ref "IC2") (pin "8") (pinfunction "GND_8") (pintype "power_in"))
      (node (ref "IC3") (pin "8") (pinfunction "GND_8") (pintype "power_in"))
      (node (ref "IC4") (pin "8") (pinfunction "GND_8") (pintype "power_in"))
      (node (ref "IC5") (pin "8") (pinfunction "GND_8") (pintype "power_in"))
      (node (ref "IC6") (pin "8") (pinfunction "GND_8") (pintype "power_in"))
      (node (ref "JP1") (pin "2") (pinfunction "2_2") (pintype "passive"))
      (node (ref "JP1") (pin "3") (pinfunction "3_3") (pintype "passive"))
      (node (ref "JP1") (pin "4") (pinfunction "4_4") (pintype "passive"))
      (node (ref "JP1") (pin "5") (pinfunction "5_5") (pintype "passive"))
      (node (ref "R11") (pin "1") (pinfunction "1_1") (pintype "passive"))
      (node (ref "R21") (pin "1") (pinfunction "1_1") (pintype "passive"))
      (node (ref "R31") (pin "1") (pinfunction "1_1") (pintype "passive"))
      (node (ref "R41") (pin "1") (pinfunction "1_1") (pintype "passive"))
      (node (ref "T1") (pin "2") (pinfunction "E_2") (pintype "passive"))
      (node (ref "T10") (pin "2") (pinfunction "E_2") (pintype "passive"))
      (node (ref "T11") (pin "2") (pinfunction "E_2") (pintype "passive"))
      (node (ref "T12") (pin "2") (pinfunction "E_2") (pintype "passive"))
      (node (ref "T13") (pin "2") (pinfunction "E_2") (pintype "passive"))
      (node (ref "T14") (pin "2") (pinfunction "E_2") (pintype "passive"))
      (node (ref "T15") (pin "2") (pinfunction "E_2") (pintype "passive"))
      (node (ref "T16") (pin "2") (pinfunction "E_2") (pintype "passive"))
      (node (ref "T17") (pin "2") (pinfunction "E_2") (pintype "passive"))
      (node (ref "T18") (pin "2") (pinfunction "E_2") (pintype "passive"))
      (node (ref "T19") (pin "2") (pinfunction "E_2") (pintype "passive"))
      (node (ref "T2") (pin "2") (pinfunction "E_2") (pintype "passive"))
      (node (ref "T20") (pin "2") (pinfunction "E_2") (pintype "passive"))
      (node (ref "T21") (pin "2") (pinfunction "E_2") (pintype "passive"))
      (node (ref "T22") (pin "2") (pinfunction "E_2") (pintype "passive"))
      (node (ref "T23") (pin "2") (pinfunction "E_2") (pintype "passive"))
      (node (ref "T24") (pin "2") (pinfunction "E_2") (pintype "passive"))
      (node (ref "T25") (pin "2") (pinfunction "E_2") (pintype "passive"))
      (node (ref "T26") (pin "2") (pinfunction "E_2") (pintype "passive"))
      (node (ref "T27") (pin "2") (pinfunction "E_2") (pintype "passive"))
      (node (ref "T28") (pin "2") (pinfunction "E_2") (pintype "passive"))
      (node (ref "T29") (pin "2") (pinfunction "E_2") (pintype "passive"))
      (node (ref "T30") (pin "2") (pinfunction "E_2") (pintype "passive"))
      (node (ref "T31") (pin "2") (pinfunction "E_2") (pintype "passive"))
      (node (ref "T32") (pin "2") (pinfunction "E_2") (pintype "passive"))
      (node (ref "T33") (pin "2") (pinfunction "E_2") (pintype "passive"))
      (node (ref "T34") (pin "2") (pinfunction "E_2") (pintype "passive"))
      (node (ref "T35") (pin "2") (pinfunction "E_2") (pintype "passive"))
      (node (ref "T36") (pin "2") (pinfunction "E_2") (pintype "passive"))
      (node (ref "T37") (pin "2") (pinfunction "E_2") (pintype "passive"))
      (node (ref "T38") (pin "2") (pinfunction "E_2") (pintype "passive"))
      (node (ref "T39") (pin "2") (pinfunction "E_2") (pintype "passive"))
      (node (ref "T40") (pin "2") (pinfunction "E_2") (pintype "passive"))
      (node (ref "T41") (pin "2") (pinfunction "E_2") (pintype "passive"))
      (node (ref "T42") (pin "2") (pinfunction "E_2") (pintype "passive"))
      (node (ref "T43") (pin "2") (pinfunction "E_2") (pintype "passive"))
      (node (ref "T44") (pin "2") (pinfunction "E_2") (pintype "passive"))
      (node (ref "T45") (pin "2") (pinfunction "E_2") (pintype "passive"))
      (node (ref "T46") (pin "2") (pinfunction "E_2") (pintype "passive"))
      (node (ref "T47") (pin "2") (pinfunction "E_2") (pintype "passive"))
      (node (ref "T48") (pin "2") (pinfunction "E_2") (pintype "passive"))
      (node (ref "T49") (pin "2") (pinfunction "E_2") (pintype "passive"))
    )
    (net (code "142") (name "Net-(GL1-A)") (class "Default")
      (node (ref "GL1") (pin "1") (pinfunction "A_1") (pintype "passive"))
      (node (ref "R1") (pin "1") (pinfunction "1_1") (pintype "passive"))
    )
    (net (code "143") (name "Net-(GL1-A1)") (class "Default")
      (node (ref "GL1") (pin "2") (pinfunction "A1_2") (pintype "passive"))
      (node (ref "T1") (pin "3") (pinfunction "C_3") (pintype "passive"))
    )
    (net (code "144") (name "Net-(GL2-A)") (class "Default")
      (node (ref "GL2") (pin "1") (pinfunction "A_1") (pintype "passive"))
      (node (ref "R2") (pin "1") (pinfunction "1_1") (pintype "passive"))
    )
    (net (code "145") (name "Net-(GL2-A1)") (class "Default")
      (node (ref "GL2") (pin "2") (pinfunction "A1_2") (pintype "passive"))
      (node (ref "T2") (pin "3") (pinfunction "C_3") (pintype "passive"))
    )
    (net (code "146") (name "Net-(IC1A-QH*)") (class "Default")
      (node (ref "IC1") (pin "9") (pinfunction "QH*_9") (pintype "tri_state"))
      (node (ref "IC2") (pin "14") (pinfunction "SER_14") (pintype "input"))
    )
    (net (code "147") (name "Net-(IC2A-QH*)") (class "Default")
      (node (ref "IC2") (pin "9") (pinfunction "QH*_9") (pintype "tri_state"))
      (node (ref "IC3") (pin "14") (pinfunction "SER_14") (pintype "input"))
    )
    (net (code "148") (name "Net-(IC3A-QH*)") (class "Default")
      (node (ref "IC3") (pin "9") (pinfunction "QH*_9") (pintype "tri_state"))
      (node (ref "IC4") (pin "14") (pinfunction "SER_14") (pintype "input"))
    )
    (net (code "149") (name "Net-(IC4A-QH*)") (class "Default")
      (node (ref "IC4") (pin "9") (pinfunction "QH*_9") (pintype "tri_state"))
      (node (ref "IC5") (pin "14") (pinfunction "SER_14") (pintype "input"))
    )
    (net (code "150") (name "Net-(IC5A-QH*)") (class "Default")
      (node (ref "IC5") (pin "9") (pinfunction "QH*_9") (pintype "tri_state"))
      (node (ref "IC6") (pin "14") (pinfunction "SER_14") (pintype "input"))
    )
    (net (code "151") (name "Net-(N1-A-PadA1)") (class "Default")
      (node (ref "N1") (pin "A1") (pinfunction "A_A1") (pintype "bidirectional"))
      (node (ref "N1") (pin "A2") (pinfunction "A_A2") (pintype "bidirectional"))
      (node (ref "R10") (pin "1") (pinfunction "1_1") (pintype "passive"))
    )
    (net (code "152") (name "Net-(N1-PadPR)") (class "Default")
      (node (ref "N1") (pin "PR") (pinfunction "PR_PR") (pintype "bidirectional"))
      (node (ref "R11") (pin "2") (pinfunction "2_2") (pintype "passive"))
    )
    (net (code "153") (name "Net-(N2-A-PadA1)") (class "Default")
      (node (ref "N2") (pin "A1") (pinfunction "A_A1") (pintype "bidirectional"))
      (node (ref "N2") (pin "A2") (pinfunction "A_A2") (pintype "bidirectional"))
      (node (ref "R20") (pin "1") (pinfunction "1_1") (pintype "passive"))
    )
    (net (code "154") (name "Net-(N2-PadPR)") (class "Default")
      (node (ref "N2") (pin "PR") (pinfunction "PR_PR") (pintype "bidirectional"))
      (node (ref "R21") (pin "2") (pinfunction "2_2") (pintype "passive"))
    )
    (net (code "155") (name "Net-(N3-A-PadA1)") (class "Default")
      (node (ref "N3") (pin "A1") (pinfunction "A_A1") (pintype "bidirectional"))
      (node (ref "N3") (pin "A2") (pinfunction "A_A2") (pintype "bidirectional"))
      (node (ref "R30") (pin "1") (pinfunction "1_1") (pintype "passive"))
    )
    (net (code "156") (name "Net-(N3-PadPR)") (class "Default")
      (node (ref "N3") (pin "PR") (pinfunction "PR_PR") (pintype "bidirectional"))
      (node (ref "R31") (pin "2") (pinfunction "2_2") (pintype "passive"))
    )
    (net (code "157") (name "Net-(N4-A-PadA1)") (class "Default")
      (node (ref "N4") (pin "A1") (pinfunction "A_A1") (pintype "bidirectional"))
      (node (ref "N4") (pin "A2") (pinfunction "A_A2") (pintype "bidirectional"))
      (node (ref "R40") (pin "1") (pinfunction "1_1") (pintype "passive"))
    )
    (net (code "158") (name "Net-(N4-PadPR)") (class "Default")
      (node (ref "N4") (pin "PR") (pinfunction "PR_PR") (pintype "bidirectional"))
      (node (ref "R41") (pin "2") (pinfunction "2_2") (pintype "passive"))
    )
    (net (code "159") (name "VDD") (class "Default")
      (node (ref "JP1") (pin "1") (pinfunction "1_1") (pintype "passive"))
      (node (ref "R1") (pin "2") (pinfunction "2_2") (pintype "passive"))
      (node (ref "R10") (pin "2") (pinfunction "2_2") (pintype "passive"))
      (node (ref "R2") (pin "2") (pinfunction "2_2") (pintype "passive"))
      (node (ref "R20") (pin "2") (pinfunction "2_2") (pintype "passive"))
      (node (ref "R30") (pin "2") (pinfunction "2_2") (pintype "passive"))
      (node (ref "R40") (pin "2") (pinfunction "2_2") (pintype "passive"))
    )
    (net (code "160") (name "unconnected-(IC6A-QH*-Pad9)") (class "Default")
      (node (ref "IC6") (pin "9") (pinfunction "QH*_9") (pintype "tri_state"))
    )
    (net (code "161") (name "unconnected-(N2-DP-PadKDP)") (class "Default")
      (node (ref "N2") (pin "KDP") (pinfunction "DP_KDP") (pintype "bidirectional"))
    )
    (net (code "162") (name "unconnected-(N3-DP-PadKDP)") (class "Default")
      (node (ref "N3") (pin "KDP") (pinfunction "DP_KDP") (pintype "bidirectional"))
    )
    (net (code "163") (name "unconnected-(N4-DP-PadKDP)") (class "Default")
      (node (ref "N4") (pin "KDP") (pinfunction "DP_KDP") (pintype "bidirectional"))
    )
    (net (code "164") (name "unconnected-(RN31-Pad7)") (class "Default")
      (node (ref "RN31") (pin "7") (pinfunction "7_7") (pintype "passive"))
    )
    (net (code "165") (name "unconnected-(RN31-Pad8)") (class "Default")
      (node (ref "RN31") (pin "8") (pinfunction "8_8") (pintype "passive"))
    )
  )
)
